# boardSchematic.net
KiCad netlist of a schematic drawn in EAGLE
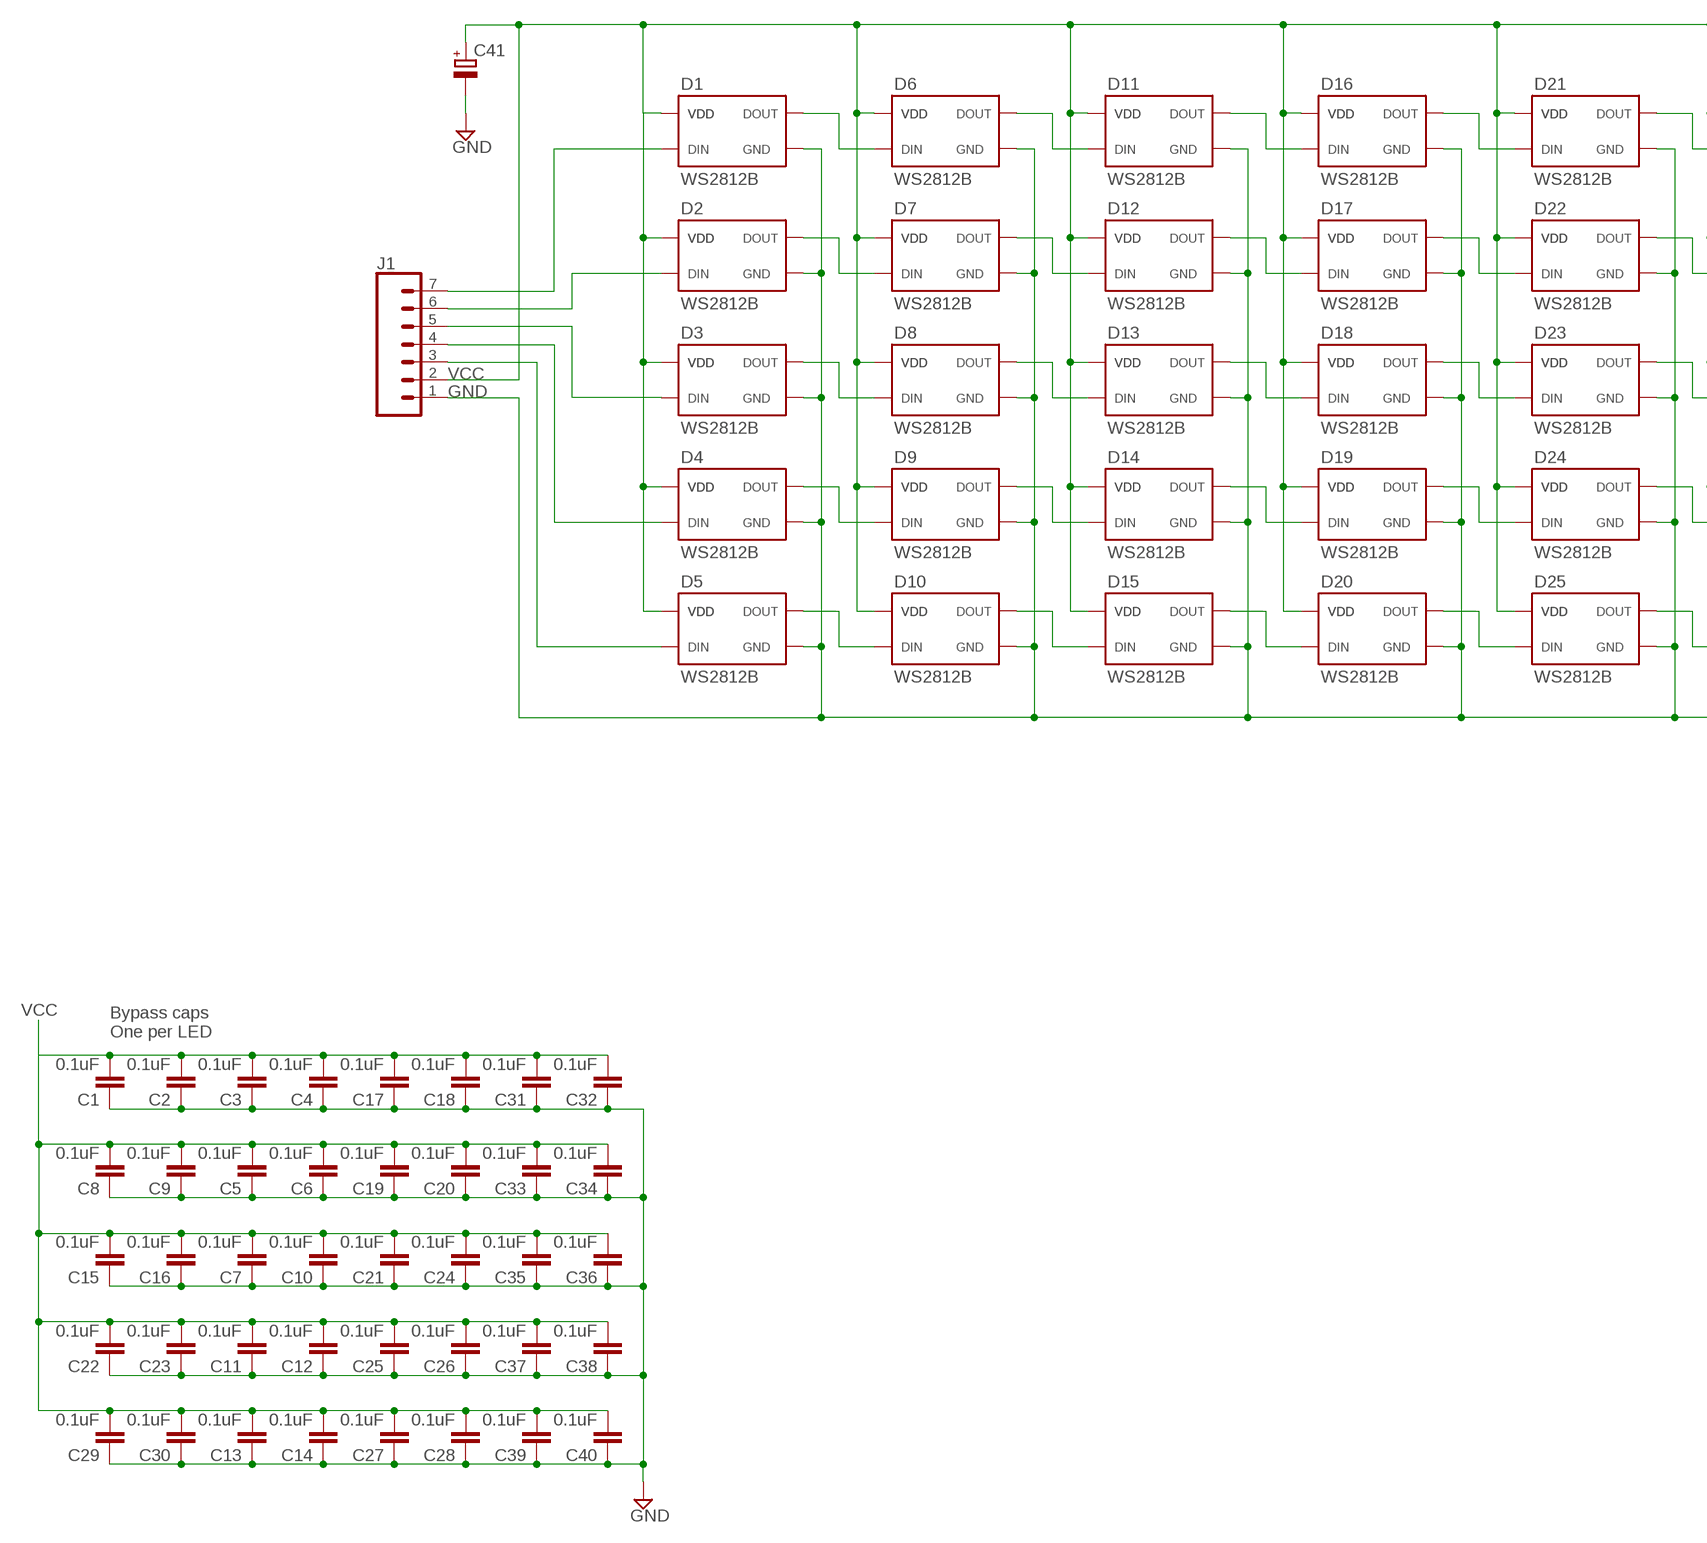
[diagram p0: schematic, sheet 1, part 1 of 2]
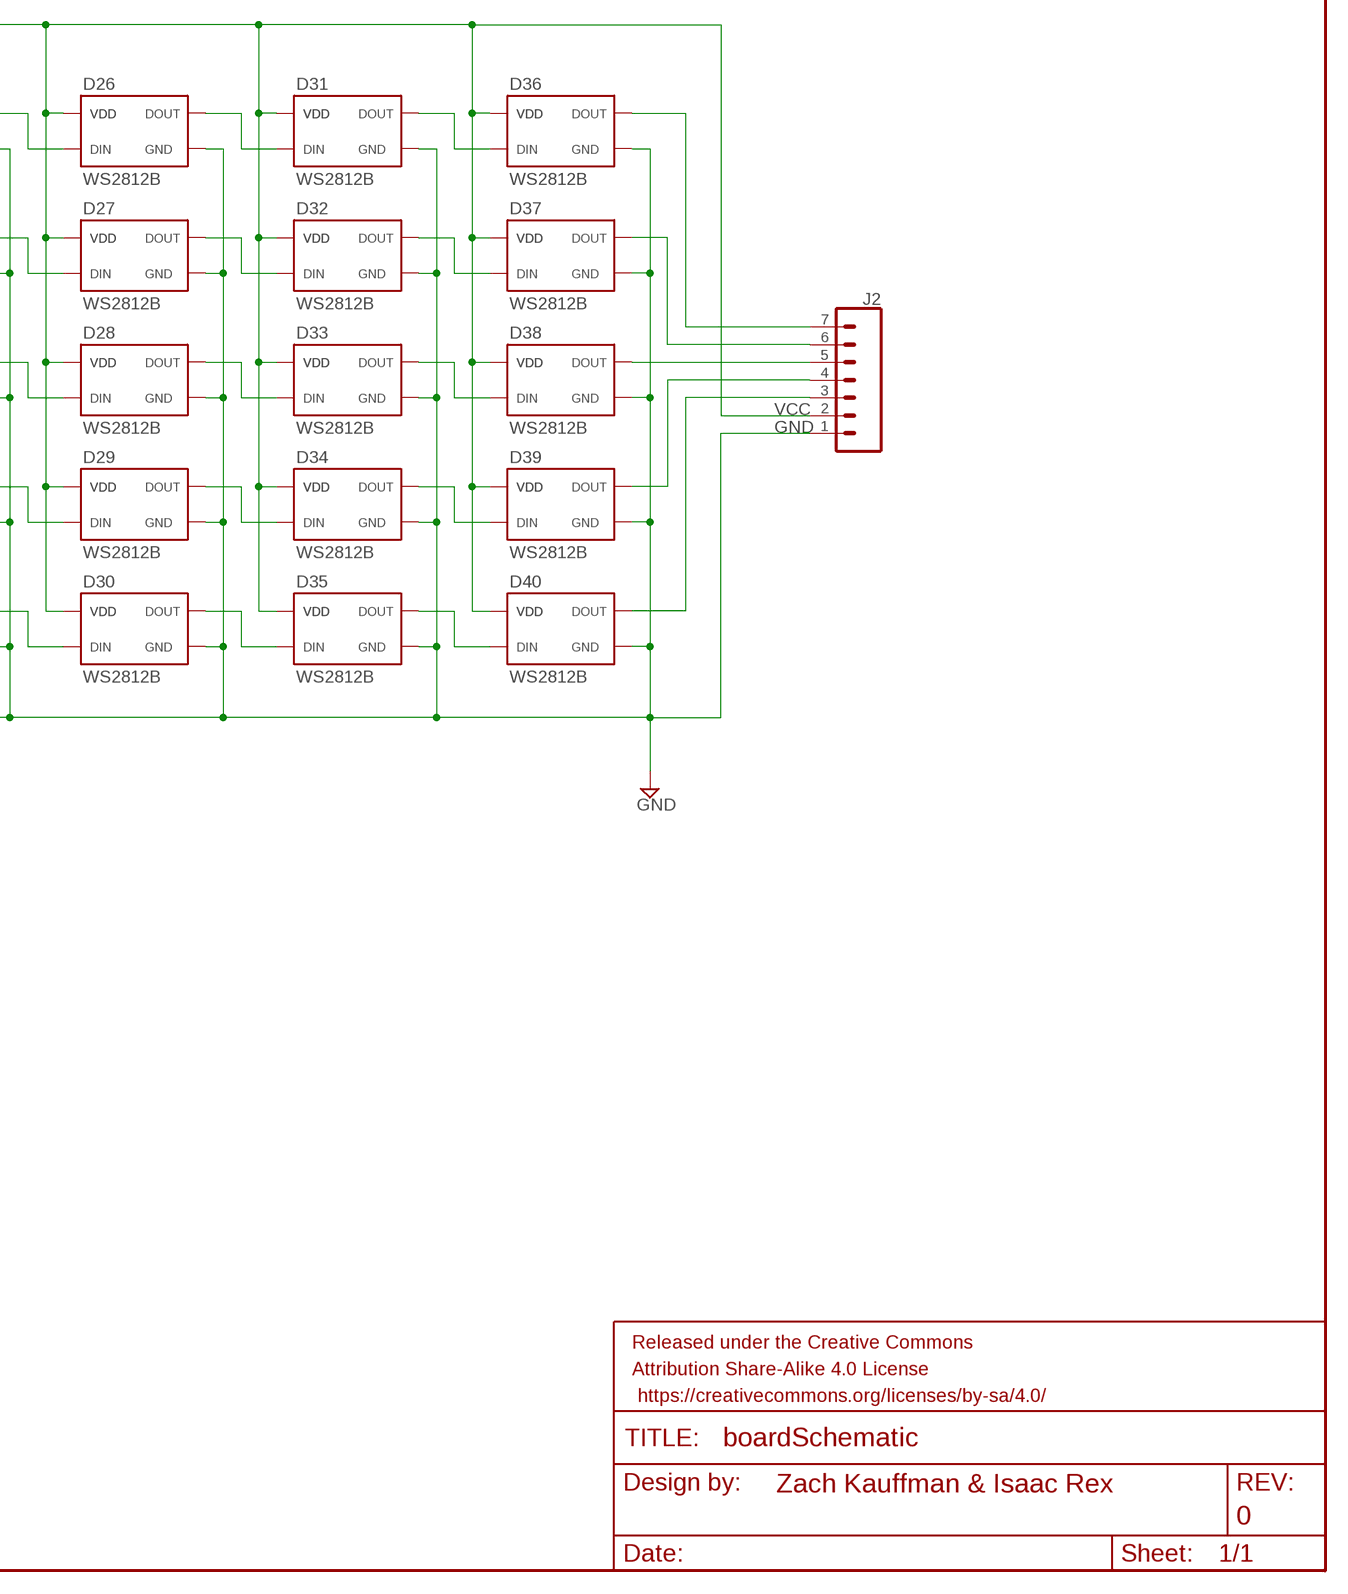
[diagram p1: schematic, sheet 1, part 2 of 2]

(export (version "E")
  (design (tool "Eeschema 10.0.6"))
  (components
    (comp (ref "C1")
      (value "0.1uF")
      (footprint "eagle-import:0603")
      (libsource (lib "eagle-import") (part "0.1UF-0603-25V-(+80/-20%)"))
    )
    (comp (ref "C2")
      (value "0.1uF")
      (footprint "eagle-import:0603")
      (libsource (lib "eagle-import") (part "0.1UF-0603-25V-(+80/-20%)"))
    )
    (comp (ref "C3")
      (value "0.1uF")
      (footprint "eagle-import:0603")
      (libsource (lib "eagle-import") (part "0.1UF-0603-25V-(+80/-20%)"))
    )
    (comp (ref "C4")
      (value "0.1uF")
      (footprint "eagle-import:0603")
      (libsource (lib "eagle-import") (part "0.1UF-0603-25V-(+80/-20%)"))
    )
    (comp (ref "C5")
      (value "0.1uF")
      (footprint "eagle-import:0603")
      (libsource (lib "eagle-import") (part "0.1UF-0603-25V-(+80/-20%)"))
    )
    (comp (ref "C6")
      (value "0.1uF")
      (footprint "eagle-import:0603")
      (libsource (lib "eagle-import") (part "0.1UF-0603-25V-(+80/-20%)"))
    )
    (comp (ref "C7")
      (value "0.1uF")
      (footprint "eagle-import:0603")
      (libsource (lib "eagle-import") (part "0.1UF-0603-25V-(+80/-20%)"))
    )
    (comp (ref "C8")
      (value "0.1uF")
      (footprint "eagle-import:0603")
      (libsource (lib "eagle-import") (part "0.1UF-0603-25V-(+80/-20%)"))
    )
    (comp (ref "C9")
      (value "0.1uF")
      (footprint "eagle-import:0603")
      (libsource (lib "eagle-import") (part "0.1UF-0603-25V-(+80/-20%)"))
    )
    (comp (ref "C10")
      (value "0.1uF")
      (footprint "eagle-import:0603")
      (libsource (lib "eagle-import") (part "0.1UF-0603-25V-(+80/-20%)"))
    )
    (comp (ref "C11")
      (value "0.1uF")
      (footprint "eagle-import:0603")
      (libsource (lib "eagle-import") (part "0.1UF-0603-25V-(+80/-20%)"))
    )
    (comp (ref "C12")
      (value "0.1uF")
      (footprint "eagle-import:0603")
      (libsource (lib "eagle-import") (part "0.1UF-0603-25V-(+80/-20%)"))
    )
    (comp (ref "C13")
      (value "0.1uF")
      (footprint "eagle-import:0603")
      (libsource (lib "eagle-import") (part "0.1UF-0603-25V-(+80/-20%)"))
    )
    (comp (ref "C14")
      (value "0.1uF")
      (footprint "eagle-import:0603")
      (libsource (lib "eagle-import") (part "0.1UF-0603-25V-(+80/-20%)"))
    )
    (comp (ref "C15")
      (value "0.1uF")
      (footprint "eagle-import:0603")
      (libsource (lib "eagle-import") (part "0.1UF-0603-25V-(+80/-20%)"))
    )
    (comp (ref "C16")
      (value "0.1uF")
      (footprint "eagle-import:0603")
      (libsource (lib "eagle-import") (part "0.1UF-0603-25V-(+80/-20%)"))
    )
    (comp (ref "C17")
      (value "0.1uF")
      (footprint "eagle-import:0603")
      (libsource (lib "eagle-import") (part "0.1UF-0603-25V-(+80/-20%)"))
    )
    (comp (ref "C18")
      (value "0.1uF")
      (footprint "eagle-import:0603")
      (libsource (lib "eagle-import") (part "0.1UF-0603-25V-(+80/-20%)"))
    )
    (comp (ref "C19")
      (value "0.1uF")
      (footprint "eagle-import:0603")
      (libsource (lib "eagle-import") (part "0.1UF-0603-25V-(+80/-20%)"))
    )
    (comp (ref "C20")
      (value "0.1uF")
      (footprint "eagle-import:0603")
      (libsource (lib "eagle-import") (part "0.1UF-0603-25V-(+80/-20%)"))
    )
    (comp (ref "C21")
      (value "0.1uF")
      (footprint "eagle-import:0603")
      (libsource (lib "eagle-import") (part "0.1UF-0603-25V-(+80/-20%)"))
    )
    (comp (ref "C22")
      (value "0.1uF")
      (footprint "eagle-import:0603")
      (libsource (lib "eagle-import") (part "0.1UF-0603-25V-(+80/-20%)"))
    )
    (comp (ref "C23")
      (value "0.1uF")
      (footprint "eagle-import:0603")
      (libsource (lib "eagle-import") (part "0.1UF-0603-25V-(+80/-20%)"))
    )
    (comp (ref "C24")
      (value "0.1uF")
      (footprint "eagle-import:0603")
      (libsource (lib "eagle-import") (part "0.1UF-0603-25V-(+80/-20%)"))
    )
    (comp (ref "C25")
      (value "0.1uF")
      (footprint "eagle-import:0603")
      (libsource (lib "eagle-import") (part "0.1UF-0603-25V-(+80/-20%)"))
    )
    (comp (ref "C26")
      (value "0.1uF")
      (footprint "eagle-import:0603")
      (libsource (lib "eagle-import") (part "0.1UF-0603-25V-(+80/-20%)"))
    )
    (comp (ref "C27")
      (value "0.1uF")
      (footprint "eagle-import:0603")
      (libsource (lib "eagle-import") (part "0.1UF-0603-25V-(+80/-20%)"))
    )
    (comp (ref "C28")
      (value "0.1uF")
      (footprint "eagle-import:0603")
      (libsource (lib "eagle-import") (part "0.1UF-0603-25V-(+80/-20%)"))
    )
    (comp (ref "C29")
      (value "0.1uF")
      (footprint "eagle-import:0603")
      (libsource (lib "eagle-import") (part "0.1UF-0603-25V-(+80/-20%)"))
    )
    (comp (ref "C30")
      (value "0.1uF")
      (footprint "eagle-import:0603")
      (libsource (lib "eagle-import") (part "0.1UF-0603-25V-(+80/-20%)"))
    )
    (comp (ref "C31")
      (value "0.1uF")
      (footprint "eagle-import:0603")
      (libsource (lib "eagle-import") (part "0.1UF-0603-25V-(+80/-20%)"))
    )
    (comp (ref "C32")
      (value "0.1uF")
      (footprint "eagle-import:0603")
      (libsource (lib "eagle-import") (part "0.1UF-0603-25V-(+80/-20%)"))
    )
    (comp (ref "C33")
      (value "0.1uF")
      (footprint "eagle-import:0603")
      (libsource (lib "eagle-import") (part "0.1UF-0603-25V-(+80/-20%)"))
    )
    (comp (ref "C34")
      (value "0.1uF")
      (footprint "eagle-import:0603")
      (libsource (lib "eagle-import") (part "0.1UF-0603-25V-(+80/-20%)"))
    )
    (comp (ref "C35")
      (value "0.1uF")
      (footprint "eagle-import:0603")
      (libsource (lib "eagle-import") (part "0.1UF-0603-25V-(+80/-20%)"))
    )
    (comp (ref "C36")
      (value "0.1uF")
      (footprint "eagle-import:0603")
      (libsource (lib "eagle-import") (part "0.1UF-0603-25V-(+80/-20%)"))
    )
    (comp (ref "C37")
      (value "0.1uF")
      (footprint "eagle-import:0603")
      (libsource (lib "eagle-import") (part "0.1UF-0603-25V-(+80/-20%)"))
    )
    (comp (ref "C38")
      (value "0.1uF")
      (footprint "eagle-import:0603")
      (libsource (lib "eagle-import") (part "0.1UF-0603-25V-(+80/-20%)"))
    )
    (comp (ref "C39")
      (value "0.1uF")
      (footprint "eagle-import:0603")
      (libsource (lib "eagle-import") (part "0.1UF-0603-25V-(+80/-20%)"))
    )
    (comp (ref "C40")
      (value "0.1uF")
      (footprint "eagle-import:0603")
      (libsource (lib "eagle-import") (part "0.1UF-0603-25V-(+80/-20%)"))
    )
    (comp (ref "C41")
      (value "CPOL-EUE2-5")
      (footprint "eagle-import:E2-5")
      (libsource (lib "eagle-import") (part "CPOL-EUE2-5"))
    )
    (comp (ref "D1")
      (value "WS2812B")
      (footprint "eagle-import:5050")
      (libsource (lib "eagle-import") (part "WS2812B"))
    )
    (comp (ref "D2")
      (value "WS2812B")
      (footprint "eagle-import:5050")
      (libsource (lib "eagle-import") (part "WS2812B"))
    )
    (comp (ref "D3")
      (value "WS2812B")
      (footprint "eagle-import:5050")
      (libsource (lib "eagle-import") (part "WS2812B"))
    )
    (comp (ref "D4")
      (value "WS2812B")
      (footprint "eagle-import:5050")
      (libsource (lib "eagle-import") (part "WS2812B"))
    )
    (comp (ref "D5")
      (value "WS2812B")
      (footprint "eagle-import:5050")
      (libsource (lib "eagle-import") (part "WS2812B"))
    )
    (comp (ref "D6")
      (value "WS2812B")
      (footprint "eagle-import:5050")
      (libsource (lib "eagle-import") (part "WS2812B"))
    )
    (comp (ref "D7")
      (value "WS2812B")
      (footprint "eagle-import:5050")
      (libsource (lib "eagle-import") (part "WS2812B"))
    )
    (comp (ref "D8")
      (value "WS2812B")
      (footprint "eagle-import:5050")
      (libsource (lib "eagle-import") (part "WS2812B"))
    )
    (comp (ref "D9")
      (value "WS2812B")
      (footprint "eagle-import:5050")
      (libsource (lib "eagle-import") (part "WS2812B"))
    )
    (comp (ref "D10")
      (value "WS2812B")
      (footprint "eagle-import:5050")
      (libsource (lib "eagle-import") (part "WS2812B"))
    )
    (comp (ref "D11")
      (value "WS2812B")
      (footprint "eagle-import:5050")
      (libsource (lib "eagle-import") (part "WS2812B"))
    )
    (comp (ref "D12")
      (value "WS2812B")
      (footprint "eagle-import:5050")
      (libsource (lib "eagle-import") (part "WS2812B"))
    )
    (comp (ref "D13")
      (value "WS2812B")
      (footprint "eagle-import:5050")
      (libsource (lib "eagle-import") (part "WS2812B"))
    )
    (comp (ref "D14")
      (value "WS2812B")
      (footprint "eagle-import:5050")
      (libsource (lib "eagle-import") (part "WS2812B"))
    )
    (comp (ref "D15")
      (value "WS2812B")
      (footprint "eagle-import:5050")
      (libsource (lib "eagle-import") (part "WS2812B"))
    )
    (comp (ref "D16")
      (value "WS2812B")
      (footprint "eagle-import:5050")
      (libsource (lib "eagle-import") (part "WS2812B"))
    )
    (comp (ref "D17")
      (value "WS2812B")
      (footprint "eagle-import:5050")
      (libsource (lib "eagle-import") (part "WS2812B"))
    )
    (comp (ref "D18")
      (value "WS2812B")
      (footprint "eagle-import:5050")
      (libsource (lib "eagle-import") (part "WS2812B"))
    )
    (comp (ref "D19")
      (value "WS2812B")
      (footprint "eagle-import:5050")
      (libsource (lib "eagle-import") (part "WS2812B"))
    )
    (comp (ref "D20")
      (value "WS2812B")
      (footprint "eagle-import:5050")
      (libsource (lib "eagle-import") (part "WS2812B"))
    )
    (comp (ref "D21")
      (value "WS2812B")
      (footprint "eagle-import:5050")
      (libsource (lib "eagle-import") (part "WS2812B"))
    )
    (comp (ref "D22")
      (value "WS2812B")
      (footprint "eagle-import:5050")
      (libsource (lib "eagle-import") (part "WS2812B"))
    )
    (comp (ref "D23")
      (value "WS2812B")
      (footprint "eagle-import:5050")
      (libsource (lib "eagle-import") (part "WS2812B"))
    )
    (comp (ref "D24")
      (value "WS2812B")
      (footprint "eagle-import:5050")
      (libsource (lib "eagle-import") (part "WS2812B"))
    )
    (comp (ref "D25")
      (value "WS2812B")
      (footprint "eagle-import:5050")
      (libsource (lib "eagle-import") (part "WS2812B"))
    )
    (comp (ref "D26")
      (value "WS2812B")
      (footprint "eagle-import:5050")
      (libsource (lib "eagle-import") (part "WS2812B"))
    )
    (comp (ref "D27")
      (value "WS2812B")
      (footprint "eagle-import:5050")
      (libsource (lib "eagle-import") (part "WS2812B"))
    )
    (comp (ref "D28")
      (value "WS2812B")
      (footprint "eagle-import:5050")
      (libsource (lib "eagle-import") (part "WS2812B"))
    )
    (comp (ref "D29")
      (value "WS2812B")
      (footprint "eagle-import:5050")
      (libsource (lib "eagle-import") (part "WS2812B"))
    )
    (comp (ref "D30")
      (value "WS2812B")
      (footprint "eagle-import:5050")
      (libsource (lib "eagle-import") (part "WS2812B"))
    )
    (comp (ref "D31")
      (value "WS2812B")
      (footprint "eagle-import:5050")
      (libsource (lib "eagle-import") (part "WS2812B"))
    )
    (comp (ref "D32")
      (value "WS2812B")
      (footprint "eagle-import:5050")
      (libsource (lib "eagle-import") (part "WS2812B"))
    )
    (comp (ref "D33")
      (value "WS2812B")
      (footprint "eagle-import:5050")
      (libsource (lib "eagle-import") (part "WS2812B"))
    )
    (comp (ref "D34")
      (value "WS2812B")
      (footprint "eagle-import:5050")
      (libsource (lib "eagle-import") (part "WS2812B"))
    )
    (comp (ref "D35")
      (value "WS2812B")
      (footprint "eagle-import:5050")
      (libsource (lib "eagle-import") (part "WS2812B"))
    )
    (comp (ref "D36")
      (value "WS2812B")
      (footprint "eagle-import:5050")
      (libsource (lib "eagle-import") (part "WS2812B"))
    )
    (comp (ref "D37")
      (value "WS2812B")
      (footprint "eagle-import:5050")
      (libsource (lib "eagle-import") (part "WS2812B"))
    )
    (comp (ref "D38")
      (value "WS2812B")
      (footprint "eagle-import:5050")
      (libsource (lib "eagle-import") (part "WS2812B"))
    )
    (comp (ref "D39")
      (value "WS2812B")
      (footprint "eagle-import:5050")
      (libsource (lib "eagle-import") (part "WS2812B"))
    )
    (comp (ref "D40")
      (value "WS2812B")
      (footprint "eagle-import:5050")
      (libsource (lib "eagle-import") (part "WS2812B"))
    )
    (comp (ref "FRAME1")
      (value "FRAME-LEDGER")
      (footprint "eagle-import:CREATIVE_COMMONS")
      (fields (field (name "DESIGNER") "Zach Kauffman & Isaac Rex") (field (name "REV") "0"))
      (libsource (lib "eagle-import") (part "FRAME-LEDGER"))
    )
    (comp (ref "J1")
      (value "CONN_07LOCK_LONGPADS")
      (footprint "eagle-import:1X07_LOCK_LONGPADS")
      (libsource (lib "eagle-import") (part "CONN_07LOCK_LONGPADS"))
    )
    (comp (ref "J2")
      (value "CONN_07LOCK_LONGPADS")
      (footprint "eagle-import:1X07_LOCK_LONGPADS")
      (libsource (lib "eagle-import") (part "CONN_07LOCK_LONGPADS"))
    )
  )
  (nets
    (net (code "1") (name "/VCC") (class "Default")
      (node (ref "C1") (pin "2") (pinfunction "2_2") (pintype "passive"))
      (node (ref "C10") (pin "2") (pinfunction "2_2") (pintype "passive"))
      (node (ref "C11") (pin "2") (pinfunction "2_2") (pintype "passive"))
      (node (ref "C12") (pin "2") (pinfunction "2_2") (pintype "passive"))
      (node (ref "C13") (pin "2") (pinfunction "2_2") (pintype "passive"))
      (node (ref "C14") (pin "2") (pinfunction "2_2") (pintype "passive"))
      (node (ref "C15") (pin "2") (pinfunction "2_2") (pintype "passive"))
      (node (ref "C16") (pin "2") (pinfunction "2_2") (pintype "passive"))
      (node (ref "C17") (pin "2") (pinfunction "2_2") (pintype "passive"))
      (node (ref "C18") (pin "2") (pinfunction "2_2") (pintype "passive"))
      (node (ref "C19") (pin "2") (pinfunction "2_2") (pintype "passive"))
      (node (ref "C2") (pin "2") (pinfunction "2_2") (pintype "passive"))
      (node (ref "C20") (pin "2") (pinfunction "2_2") (pintype "passive"))
      (node (ref "C21") (pin "2") (pinfunction "2_2") (pintype "passive"))
      (node (ref "C22") (pin "2") (pinfunction "2_2") (pintype "passive"))
      (node (ref "C23") (pin "2") (pinfunction "2_2") (pintype "passive"))
      (node (ref "C24") (pin "2") (pinfunction "2_2") (pintype "passive"))
      (node (ref "C25") (pin "2") (pinfunction "2_2") (pintype "passive"))
      (node (ref "C26") (pin "2") (pinfunction "2_2") (pintype "passive"))
      (node (ref "C27") (pin "2") (pinfunction "2_2") (pintype "passive"))
      (node (ref "C28") (pin "2") (pinfunction "2_2") (pintype "passive"))
      (node (ref "C29") (pin "2") (pinfunction "2_2") (pintype "passive"))
      (node (ref "C3") (pin "2") (pinfunction "2_2") (pintype "passive"))
      (node (ref "C30") (pin "2") (pinfunction "2_2") (pintype "passive"))
      (node (ref "C31") (pin "2") (pinfunction "2_2") (pintype "passive"))
      (node (ref "C32") (pin "2") (pinfunction "2_2") (pintype "passive"))
      (node (ref "C33") (pin "2") (pinfunction "2_2") (pintype "passive"))
      (node (ref "C34") (pin "2") (pinfunction "2_2") (pintype "passive"))
      (node (ref "C35") (pin "2") (pinfunction "2_2") (pintype "passive"))
      (node (ref "C36") (pin "2") (pinfunction "2_2") (pintype "passive"))
      (node (ref "C37") (pin "2") (pinfunction "2_2") (pintype "passive"))
      (node (ref "C38") (pin "2") (pinfunction "2_2") (pintype "passive"))
      (node (ref "C39") (pin "2") (pinfunction "2_2") (pintype "passive"))
      (node (ref "C4") (pin "2") (pinfunction "2_2") (pintype "passive"))
      (node (ref "C40") (pin "2") (pinfunction "2_2") (pintype "passive"))
      (node (ref "C41") (pin "+") (pinfunction "+_+") (pintype "passive"))
      (node (ref "C5") (pin "2") (pinfunction "2_2") (pintype "passive"))
      (node (ref "C6") (pin "2") (pinfunction "2_2") (pintype "passive"))
      (node (ref "C7") (pin "2") (pinfunction "2_2") (pintype "passive"))
      (node (ref "C8") (pin "2") (pinfunction "2_2") (pintype "passive"))
      (node (ref "C9") (pin "2") (pinfunction "2_2") (pintype "passive"))
      (node (ref "D1") (pin "VDD") (pinfunction "VDD_VDD") (pintype "bidirectional"))
      (node (ref "D10") (pin "VDD") (pinfunction "VDD_VDD") (pintype "bidirectional"))
      (node (ref "D11") (pin "VDD") (pinfunction "VDD_VDD") (pintype "bidirectional"))
      (node (ref "D12") (pin "VDD") (pinfunction "VDD_VDD") (pintype "bidirectional"))
      (node (ref "D13") (pin "VDD") (pinfunction "VDD_VDD") (pintype "bidirectional"))
      (node (ref "D14") (pin "VDD") (pinfunction "VDD_VDD") (pintype "bidirectional"))
      (node (ref "D15") (pin "VDD") (pinfunction "VDD_VDD") (pintype "bidirectional"))
      (node (ref "D16") (pin "VDD") (pinfunction "VDD_VDD") (pintype "bidirectional"))
      (node (ref "D17") (pin "VDD") (pinfunction "VDD_VDD") (pintype "bidirectional"))
      (node (ref "D18") (pin "VDD") (pinfunction "VDD_VDD") (pintype "bidirectional"))
      (node (ref "D19") (pin "VDD") (pinfunction "VDD_VDD") (pintype "bidirectional"))
      (node (ref "D2") (pin "VDD") (pinfunction "VDD_VDD") (pintype "bidirectional"))
      (node (ref "D20") (pin "VDD") (pinfunction "VDD_VDD") (pintype "bidirectional"))
      (node (ref "D21") (pin "VDD") (pinfunction "VDD_VDD") (pintype "bidirectional"))
      (node (ref "D22") (pin "VDD") (pinfunction "VDD_VDD") (pintype "bidirectional"))
      (node (ref "D23") (pin "VDD") (pinfunction "VDD_VDD") (pintype "bidirectional"))
      (node (ref "D24") (pin "VDD") (pinfunction "VDD_VDD") (pintype "bidirectional"))
      (node (ref "D25") (pin "VDD") (pinfunction "VDD_VDD") (pintype "bidirectional"))
      (node (ref "D26") (pin "VDD") (pinfunction "VDD_VDD") (pintype "bidirectional"))
      (node (ref "D27") (pin "VDD") (pinfunction "VDD_VDD") (pintype "bidirectional"))
      (node (ref "D28") (pin "VDD") (pinfunction "VDD_VDD") (pintype "bidirectional"))
      (node (ref "D29") (pin "VDD") (pinfunction "VDD_VDD") (pintype "bidirectional"))
      (node (ref "D3") (pin "VDD") (pinfunction "VDD_VDD") (pintype "bidirectional"))
      (node (ref "D30") (pin "VDD") (pinfunction "VDD_VDD") (pintype "bidirectional"))
      (node (ref "D31") (pin "VDD") (pinfunction "VDD_VDD") (pintype "bidirectional"))
      (node (ref "D32") (pin "VDD") (pinfunction "VDD_VDD") (pintype "bidirectional"))
      (node (ref "D33") (pin "VDD") (pinfunction "VDD_VDD") (pintype "bidirectional"))
      (node (ref "D34") (pin "VDD") (pinfunction "VDD_VDD") (pintype "bidirectional"))
      (node (ref "D35") (pin "VDD") (pinfunction "VDD_VDD") (pintype "bidirectional"))
      (node (ref "D36") (pin "VDD") (pinfunction "VDD_VDD") (pintype "bidirectional"))
      (node (ref "D37") (pin "VDD") (pinfunction "VDD_VDD") (pintype "bidirectional"))
      (node (ref "D38") (pin "VDD") (pinfunction "VDD_VDD") (pintype "bidirectional"))
      (node (ref "D39") (pin "VDD") (pinfunction "VDD_VDD") (pintype "bidirectional"))
      (node (ref "D4") (pin "VDD") (pinfunction "VDD_VDD") (pintype "bidirectional"))
      (node (ref "D40") (pin "VDD") (pinfunction "VDD_VDD") (pintype "bidirectional"))
      (node (ref "D5") (pin "VDD") (pinfunction "VDD_VDD") (pintype "bidirectional"))
      (node (ref "D6") (pin "VDD") (pinfunction "VDD_VDD") (pintype "bidirectional"))
      (node (ref "D7") (pin "VDD") (pinfunction "VDD_VDD") (pintype "bidirectional"))
      (node (ref "D8") (pin "VDD") (pinfunction "VDD_VDD") (pintype "bidirectional"))
      (node (ref "D9") (pin "VDD") (pinfunction "VDD_VDD") (pintype "bidirectional"))
      (node (ref "J1") (pin "2") (pinfunction "2_2") (pintype "passive"))
      (node (ref "J2") (pin "2") (pinfunction "2_2") (pintype "passive"))
    )
    (net (code "2") (name "GND") (class "Default")
      (node (ref "C1") (pin "1") (pinfunction "1_1") (pintype "passive"))
      (node (ref "C10") (pin "1") (pinfunction "1_1") (pintype "passive"))
      (node (ref "C11") (pin "1") (pinfunction "1_1") (pintype "passive"))
      (node (ref "C12") (pin "1") (pinfunction "1_1") (pintype "passive"))
      (node (ref "C13") (pin "1") (pinfunction "1_1") (pintype "passive"))
      (node (ref "C14") (pin "1") (pinfunction "1_1") (pintype "passive"))
      (node (ref "C15") (pin "1") (pinfunction "1_1") (pintype "passive"))
      (node (ref "C16") (pin "1") (pinfunction "1_1") (pintype "passive"))
      (node (ref "C17") (pin "1") (pinfunction "1_1") (pintype "passive"))
      (node (ref "C18") (pin "1") (pinfunction "1_1") (pintype "passive"))
      (node (ref "C19") (pin "1") (pinfunction "1_1") (pintype "passive"))
      (node (ref "C2") (pin "1") (pinfunction "1_1") (pintype "passive"))
      (node (ref "C20") (pin "1") (pinfunction "1_1") (pintype "passive"))
      (node (ref "C21") (pin "1") (pinfunction "1_1") (pintype "passive"))
      (node (ref "C22") (pin "1") (pinfunction "1_1") (pintype "passive"))
      (node (ref "C23") (pin "1") (pinfunction "1_1") (pintype "passive"))
      (node (ref "C24") (pin "1") (pinfunction "1_1") (pintype "passive"))
      (node (ref "C25") (pin "1") (pinfunction "1_1") (pintype "passive"))
      (node (ref "C26") (pin "1") (pinfunction "1_1") (pintype "passive"))
      (node (ref "C27") (pin "1") (pinfunction "1_1") (pintype "passive"))
      (node (ref "C28") (pin "1") (pinfunction "1_1") (pintype "passive"))
      (node (ref "C29") (pin "1") (pinfunction "1_1") (pintype "passive"))
      (node (ref "C3") (pin "1") (pinfunction "1_1") (pintype "passive"))
      (node (ref "C30") (pin "1") (pinfunction "1_1") (pintype "passive"))
      (node (ref "C31") (pin "1") (pinfunction "1_1") (pintype "passive"))
      (node (ref "C32") (pin "1") (pinfunction "1_1") (pintype "passive"))
      (node (ref "C33") (pin "1") (pinfunction "1_1") (pintype "passive"))
      (node (ref "C34") (pin "1") (pinfunction "1_1") (pintype "passive"))
      (node (ref "C35") (pin "1") (pinfunction "1_1") (pintype "passive"))
      (node (ref "C36") (pin "1") (pinfunction "1_1") (pintype "passive"))
      (node (ref "C37") (pin "1") (pinfunction "1_1") (pintype "passive"))
      (node (ref "C38") (pin "1") (pinfunction "1_1") (pintype "passive"))
      (node (ref "C39") (pin "1") (pinfunction "1_1") (pintype "passive"))
      (node (ref "C4") (pin "1") (pinfunction "1_1") (pintype "passive"))
      (node (ref "C40") (pin "1") (pinfunction "1_1") (pintype "passive"))
      (node (ref "C41") (pin "-") (pinfunction "-_-") (pintype "passive"))
      (node (ref "C5") (pin "1") (pinfunction "1_1") (pintype "passive"))
      (node (ref "C6") (pin "1") (pinfunction "1_1") (pintype "passive"))
      (node (ref "C7") (pin "1") (pinfunction "1_1") (pintype "passive"))
      (node (ref "C8") (pin "1") (pinfunction "1_1") (pintype "passive"))
      (node (ref "C9") (pin "1") (pinfunction "1_1") (pintype "passive"))
      (node (ref "D1") (pin "VSS") (pinfunction "GND_VSS") (pintype "bidirectional"))
      (node (ref "D10") (pin "VSS") (pinfunction "GND_VSS") (pintype "bidirectional"))
      (node (ref "D11") (pin "VSS") (pinfunction "GND_VSS") (pintype "bidirectional"))
      (node (ref "D12") (pin "VSS") (pinfunction "GND_VSS") (pintype "bidirectional"))
      (node (ref "D13") (pin "VSS") (pinfunction "GND_VSS") (pintype "bidirectional"))
      (node (ref "D14") (pin "VSS") (pinfunction "GND_VSS") (pintype "bidirectional"))
      (node (ref "D15") (pin "VSS") (pinfunction "GND_VSS") (pintype "bidirectional"))
      (node (ref "D16") (pin "VSS") (pinfunction "GND_VSS") (pintype "bidirectional"))
      (node (ref "D17") (pin "VSS") (pinfunction "GND_VSS") (pintype "bidirectional"))
      (node (ref "D18") (pin "VSS") (pinfunction "GND_VSS") (pintype "bidirectional"))
      (node (ref "D19") (pin "VSS") (pinfunction "GND_VSS") (pintype "bidirectional"))
      (node (ref "D2") (pin "VSS") (pinfunction "GND_VSS") (pintype "bidirectional"))
      (node (ref "D20") (pin "VSS") (pinfunction "GND_VSS") (pintype "bidirectional"))
      (node (ref "D21") (pin "VSS") (pinfunction "GND_VSS") (pintype "bidirectional"))
      (node (ref "D22") (pin "VSS") (pinfunction "GND_VSS") (pintype "bidirectional"))
      (node (ref "D23") (pin "VSS") (pinfunction "GND_VSS") (pintype "bidirectional"))
      (node (ref "D24") (pin "VSS") (pinfunction "GND_VSS") (pintype "bidirectional"))
      (node (ref "D25") (pin "VSS") (pinfunction "GND_VSS") (pintype "bidirectional"))
      (node (ref "D26") (pin "VSS") (pinfunction "GND_VSS") (pintype "bidirectional"))
      (node (ref "D27") (pin "VSS") (pinfunction "GND_VSS") (pintype "bidirectional"))
      (node (ref "D28") (pin "VSS") (pinfunction "GND_VSS") (pintype "bidirectional"))
      (node (ref "D29") (pin "VSS") (pinfunction "GND_VSS") (pintype "bidirectional"))
      (node (ref "D3") (pin "VSS") (pinfunction "GND_VSS") (pintype "bidirectional"))
      (node (ref "D30") (pin "VSS") (pinfunction "GND_VSS") (pintype "bidirectional"))
      (node (ref "D31") (pin "VSS") (pinfunction "GND_VSS") (pintype "bidirectional"))
      (node (ref "D32") (pin "VSS") (pinfunction "GND_VSS") (pintype "bidirectional"))
      (node (ref "D33") (pin "VSS") (pinfunction "GND_VSS") (pintype "bidirectional"))
      (node (ref "D34") (pin "VSS") (pinfunction "GND_VSS") (pintype "bidirectional"))
      (node (ref "D35") (pin "VSS") (pinfunction "GND_VSS") (pintype "bidirectional"))
      (node (ref "D36") (pin "VSS") (pinfunction "GND_VSS") (pintype "bidirectional"))
      (node (ref "D37") (pin "VSS") (pinfunction "GND_VSS") (pintype "bidirectional"))
      (node (ref "D38") (pin "VSS") (pinfunction "GND_VSS") (pintype "bidirectional"))
      (node (ref "D39") (pin "VSS") (pinfunction "GND_VSS") (pintype "bidirectional"))
      (node (ref "D4") (pin "VSS") (pinfunction "GND_VSS") (pintype "bidirectional"))
      (node (ref "D40") (pin "VSS") (pinfunction "GND_VSS") (pintype "bidirectional"))
      (node (ref "D5") (pin "VSS") (pinfunction "GND_VSS") (pintype "bidirectional"))
      (node (ref "D6") (pin "VSS") (pinfunction "GND_VSS") (pintype "bidirectional"))
      (node (ref "D7") (pin "VSS") (pinfunction "GND_VSS") (pintype "bidirectional"))
      (node (ref "D8") (pin "VSS") (pinfunction "GND_VSS") (pintype "bidirectional"))
      (node (ref "D9") (pin "VSS") (pinfunction "GND_VSS") (pintype "bidirectional"))
      (node (ref "J1") (pin "1") (pinfunction "1_1") (pintype "passive"))
      (node (ref "J2") (pin "1") (pinfunction "1_1") (pintype "passive"))
    )
    (net (code "3") (name "Net-(D1-PadDIN)") (class "Default")
      (node (ref "D1") (pin "DIN") (pinfunction "DIN_DIN") (pintype "bidirectional"))
      (node (ref "J1") (pin "7") (pinfunction "7_7") (pintype "passive"))
    )
    (net (code "4") (name "Net-(D1-PadDOUT)") (class "Default")
      (node (ref "D1") (pin "DOUT") (pinfunction "DOUT_DOUT") (pintype "bidirectional"))
      (node (ref "D6") (pin "DIN") (pinfunction "DIN_DIN") (pintype "bidirectional"))
    )
    (net (code "5") (name "Net-(D2-PadDIN)") (class "Default")
      (node (ref "D2") (pin "DIN") (pinfunction "DIN_DIN") (pintype "bidirectional"))
      (node (ref "J1") (pin "6") (pinfunction "6_6") (pintype "passive"))
    )
    (net (code "6") (name "Net-(D2-PadDOUT)") (class "Default")
      (node (ref "D2") (pin "DOUT") (pinfunction "DOUT_DOUT") (pintype "bidirectional"))
      (node (ref "D7") (pin "DIN") (pinfunction "DIN_DIN") (pintype "bidirectional"))
    )
    (net (code "7") (name "Net-(D3-PadDIN)") (class "Default")
      (node (ref "D3") (pin "DIN") (pinfunction "DIN_DIN") (pintype "bidirectional"))
      (node (ref "J1") (pin "5") (pinfunction "5_5") (pintype "passive"))
    )
    (net (code "8") (name "Net-(D3-PadDOUT)") (class "Default")
      (node (ref "D3") (pin "DOUT") (pinfunction "DOUT_DOUT") (pintype "bidirectional"))
      (node (ref "D8") (pin "DIN") (pinfunction "DIN_DIN") (pintype "bidirectional"))
    )
    (net (code "9") (name "Net-(D4-PadDIN)") (class "Default")
      (node (ref "D4") (pin "DIN") (pinfunction "DIN_DIN") (pintype "bidirectional"))
      (node (ref "J1") (pin "4") (pinfunction "4_4") (pintype "passive"))
    )
    (net (code "10") (name "Net-(D4-PadDOUT)") (class "Default")
      (node (ref "D4") (pin "DOUT") (pinfunction "DOUT_DOUT") (pintype "bidirectional"))
      (node (ref "D9") (pin "DIN") (pinfunction "DIN_DIN") (pintype "bidirectional"))
    )
    (net (code "11") (name "Net-(D5-PadDIN)") (class "Default")
      (node (ref "D5") (pin "DIN") (pinfunction "DIN_DIN") (pintype "bidirectional"))
      (node (ref "J1") (pin "3") (pinfunction "3_3") (pintype "passive"))
    )
    (net (code "12") (name "Net-(D10-PadDIN)") (class "Default")
      (node (ref "D10") (pin "DIN") (pinfunction "DIN_DIN") (pintype "bidirectional"))
      (node (ref "D5") (pin "DOUT") (pinfunction "DOUT_DOUT") (pintype "bidirectional"))
    )
    (net (code "13") (name "Net-(D10-PadDOUT)") (class "Default")
      (node (ref "D10") (pin "DOUT") (pinfunction "DOUT_DOUT") (pintype "bidirectional"))
      (node (ref "D15") (pin "DIN") (pinfunction "DIN_DIN") (pintype "bidirectional"))
    )
    (net (code "14") (name "Net-(D11-PadDIN)") (class "Default")
      (node (ref "D11") (pin "DIN") (pinfunction "DIN_DIN") (pintype "bidirectional"))
      (node (ref "D6") (pin "DOUT") (pinfunction "DOUT_DOUT") (pintype "bidirectional"))
    )
    (net (code "15") (name "Net-(D11-PadDOUT)") (class "Default")
      (node (ref "D11") (pin "DOUT") (pinfunction "DOUT_DOUT") (pintype "bidirectional"))
      (node (ref "D16") (pin "DIN") (pinfunction "DIN_DIN") (pintype "bidirectional"))
    )
    (net (code "16") (name "Net-(D12-PadDIN)") (class "Default")
      (node (ref "D12") (pin "DIN") (pinfunction "DIN_DIN") (pintype "bidirectional"))
      (node (ref "D7") (pin "DOUT") (pinfunction "DOUT_DOUT") (pintype "bidirectional"))
    )
    (net (code "17") (name "Net-(D12-PadDOUT)") (class "Default")
      (node (ref "D12") (pin "DOUT") (pinfunction "DOUT_DOUT") (pintype "bidirectional"))
      (node (ref "D17") (pin "DIN") (pinfunction "DIN_DIN") (pintype "bidirectional"))
    )
    (net (code "18") (name "Net-(D13-PadDIN)") (class "Default")
      (node (ref "D13") (pin "DIN") (pinfunction "DIN_DIN") (pintype "bidirectional"))
      (node (ref "D8") (pin "DOUT") (pinfunction "DOUT_DOUT") (pintype "bidirectional"))
    )
    (net (code "19") (name "Net-(D13-PadDOUT)") (class "Default")
      (node (ref "D13") (pin "DOUT") (pinfunction "DOUT_DOUT") (pintype "bidirectional"))
      (node (ref "D18") (pin "DIN") (pinfunction "DIN_DIN") (pintype "bidirectional"))
    )
    (net (code "20") (name "Net-(D14-PadDIN)") (class "Default")
      (node (ref "D14") (pin "DIN") (pinfunction "DIN_DIN") (pintype "bidirectional"))
      (node (ref "D9") (pin "DOUT") (pinfunction "DOUT_DOUT") (pintype "bidirectional"))
    )
    (net (code "21") (name "Net-(D14-PadDOUT)") (class "Default")
      (node (ref "D14") (pin "DOUT") (pinfunction "DOUT_DOUT") (pintype "bidirectional"))
      (node (ref "D19") (pin "DIN") (pinfunction "DIN_DIN") (pintype "bidirectional"))
    )
    (net (code "22") (name "Net-(D15-PadDOUT)") (class "Default")
      (node (ref "D15") (pin "DOUT") (pinfunction "DOUT_DOUT") (pintype "bidirectional"))
      (node (ref "D20") (pin "DIN") (pinfunction "DIN_DIN") (pintype "bidirectional"))
    )
    (net (code "23") (name "Net-(D16-PadDOUT)") (class "Default")
      (node (ref "D16") (pin "DOUT") (pinfunction "DOUT_DOUT") (pintype "bidirectional"))
      (node (ref "D21") (pin "DIN") (pinfunction "DIN_DIN") (pintype "bidirectional"))
    )
    (net (code "24") (name "Net-(D17-PadDOUT)") (class "Default")
      (node (ref "D17") (pin "DOUT") (pinfunction "DOUT_DOUT") (pintype "bidirectional"))
      (node (ref "D22") (pin "DIN") (pinfunction "DIN_DIN") (pintype "bidirectional"))
    )
    (net (code "25") (name "Net-(D18-PadDOUT)") (class "Default")
      (node (ref "D18") (pin "DOUT") (pinfunction "DOUT_DOUT") (pintype "bidirectional"))
      (node (ref "D23") (pin "DIN") (pinfunction "DIN_DIN") (pintype "bidirectional"))
    )
    (net (code "26") (name "Net-(D19-PadDOUT)") (class "Default")
      (node (ref "D19") (pin "DOUT") (pinfunction "DOUT_DOUT") (pintype "bidirectional"))
      (node (ref "D24") (pin "DIN") (pinfunction "DIN_DIN") (pintype "bidirectional"))
    )
    (net (code "27") (name "Net-(D20-PadDOUT)") (class "Default")
      (node (ref "D20") (pin "DOUT") (pinfunction "DOUT_DOUT") (pintype "bidirectional"))
      (node (ref "D25") (pin "DIN") (pinfunction "DIN_DIN") (pintype "bidirectional"))
    )
    (net (code "28") (name "Net-(D21-PadDOUT)") (class "Default")
      (node (ref "D21") (pin "DOUT") (pinfunction "DOUT_DOUT") (pintype "bidirectional"))
      (node (ref "D26") (pin "DIN") (pinfunction "DIN_DIN") (pintype "bidirectional"))
    )
    (net (code "29") (name "Net-(D22-PadDOUT)") (class "Default")
      (node (ref "D22") (pin "DOUT") (pinfunction "DOUT_DOUT") (pintype "bidirectional"))
      (node (ref "D27") (pin "DIN") (pinfunction "DIN_DIN") (pintype "bidirectional"))
    )
    (net (code "30") (name "Net-(D23-PadDOUT)") (class "Default")
      (node (ref "D23") (pin "DOUT") (pinfunction "DOUT_DOUT") (pintype "bidirectional"))
      (node (ref "D28") (pin "DIN") (pinfunction "DIN_DIN") (pintype "bidirectional"))
    )
    (net (code "31") (name "Net-(D24-PadDOUT)") (class "Default")
      (node (ref "D24") (pin "DOUT") (pinfunction "DOUT_DOUT") (pintype "bidirectional"))
      (node (ref "D29") (pin "DIN") (pinfunction "DIN_DIN") (pintype "bidirectional"))
    )
    (net (code "32") (name "Net-(D25-PadDOUT)") (class "Default")
      (node (ref "D25") (pin "DOUT") (pinfunction "DOUT_DOUT") (pintype "bidirectional"))
      (node (ref "D30") (pin "DIN") (pinfunction "DIN_DIN") (pintype "bidirectional"))
    )
    (net (code "33") (name "Net-(D26-PadDOUT)") (class "Default")
      (node (ref "D26") (pin "DOUT") (pinfunction "DOUT_DOUT") (pintype "bidirectional"))
      (node (ref "D31") (pin "DIN") (pinfunction "DIN_DIN") (pintype "bidirectional"))
    )
    (net (code "34") (name "Net-(D27-PadDOUT)") (class "Default")
      (node (ref "D27") (pin "DOUT") (pinfunction "DOUT_DOUT") (pintype "bidirectional"))
      (node (ref "D32") (pin "DIN") (pinfunction "DIN_DIN") (pintype "bidirectional"))
    )
    (net (code "35") (name "Net-(D28-PadDOUT)") (class "Default")
      (node (ref "D28") (pin "DOUT") (pinfunction "DOUT_DOUT") (pintype "bidirectional"))
      (node (ref "D33") (pin "DIN") (pinfunction "DIN_DIN") (pintype "bidirectional"))
    )
    (net (code "36") (name "Net-(D29-PadDOUT)") (class "Default")
      (node (ref "D29") (pin "DOUT") (pinfunction "DOUT_DOUT") (pintype "bidirectional"))
      (node (ref "D34") (pin "DIN") (pinfunction "DIN_DIN") (pintype "bidirectional"))
    )
    (net (code "37") (name "Net-(D30-PadDOUT)") (class "Default")
      (node (ref "D30") (pin "DOUT") (pinfunction "DOUT_DOUT") (pintype "bidirectional"))
      (node (ref "D35") (pin "DIN") (pinfunction "DIN_DIN") (pintype "bidirectional"))
    )
    (net (code "38") (name "Net-(D31-PadDOUT)") (class "Default")
      (node (ref "D31") (pin "DOUT") (pinfunction "DOUT_DOUT") (pintype "bidirectional"))
      (node (ref "D36") (pin "DIN") (pinfunction "DIN_DIN") (pintype "bidirectional"))
    )
    (net (code "39") (name "Net-(D32-PadDOUT)") (class "Default")
      (node (ref "D32") (pin "DOUT") (pinfunction "DOUT_DOUT") (pintype "bidirectional"))
      (node (ref "D37") (pin "DIN") (pinfunction "DIN_DIN") (pintype "bidirectional"))
    )
    (net (code "40") (name "Net-(D33-PadDOUT)") (class "Default")
      (node (ref "D33") (pin "DOUT") (pinfunction "DOUT_DOUT") (pintype "bidirectional"))
      (node (ref "D38") (pin "DIN") (pinfunction "DIN_DIN") (pintype "bidirectional"))
    )
    (net (code "41") (name "Net-(D34-PadDOUT)") (class "Default")
      (node (ref "D34") (pin "DOUT") (pinfunction "DOUT_DOUT") (pintype "bidirectional"))
      (node (ref "D39") (pin "DIN") (pinfunction "DIN_DIN") (pintype "bidirectional"))
    )
    (net (code "42") (name "Net-(D35-PadDOUT)") (class "Default")
      (node (ref "D35") (pin "DOUT") (pinfunction "DOUT_DOUT") (pintype "bidirectional"))
      (node (ref "D40") (pin "DIN") (pinfunction "DIN_DIN") (pintype "bidirectional"))
    )
    (net (code "43") (name "Net-(D36-PadDOUT)") (class "Default")
      (node (ref "D36") (pin "DOUT") (pinfunction "DOUT_DOUT") (pintype "bidirectional"))
      (node (ref "J2") (pin "7") (pinfunction "7_7") (pintype "passive"))
    )
    (net (code "44") (name "Net-(D37-PadDOUT)") (class "Default")
      (node (ref "D37") (pin "DOUT") (pinfunction "DOUT_DOUT") (pintype "bidirectional"))
      (node (ref "J2") (pin "6") (pinfunction "6_6") (pintype "passive"))
    )
    (net (code "45") (name "Net-(D38-PadDOUT)") (class "Default")
      (node (ref "D38") (pin "DOUT") (pinfunction "DOUT_DOUT") (pintype "bidirectional"))
      (node (ref "J2") (pin "5") (pinfunction "5_5") (pintype "passive"))
    )
    (net (code "46") (name "Net-(D39-PadDOUT)") (class "Default")
      (node (ref "D39") (pin "DOUT") (pinfunction "DOUT_DOUT") (pintype "bidirectional"))
      (node (ref "J2") (pin "4") (pinfunction "4_4") (pintype "passive"))
    )
    (net (code "47") (name "Net-(D40-PadDOUT)") (class "Default")
      (node (ref "D40") (pin "DOUT") (pinfunction "DOUT_DOUT") (pintype "bidirectional"))
      (node (ref "J2") (pin "3") (pinfunction "3_3") (pintype "passive"))
    )
  )
)
